# Flatcable_to_wires.net
KiCad netlist of a schematic drawn in Altium Designer
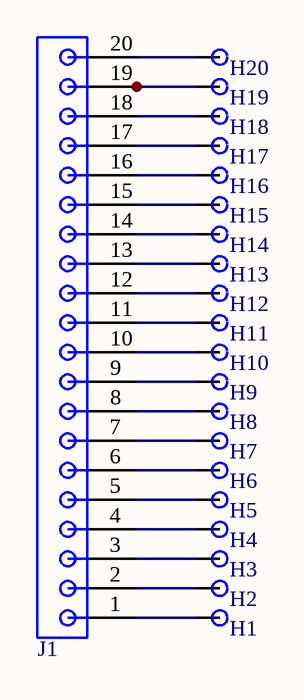
[diagram p0: Flatcable_to_wires.SchDoc]

(export (version "E")
  (design (tool "Eeschema 10.0.6"))
  (components
    (comp (ref "H1") (value "PAD") (footprint "PAD") (libsource (lib "sample_holder_library") (part "PAD")))
    (comp (ref "H2") (value "PAD") (footprint "PAD") (libsource (lib "sample_holder_library") (part "PAD")))
    (comp (ref "H3") (value "PAD") (footprint "PAD") (libsource (lib "sample_holder_library") (part "PAD")))
    (comp (ref "H4") (value "PAD") (footprint "PAD") (libsource (lib "sample_holder_library") (part "PAD")))
    (comp (ref "H5") (value "PAD") (footprint "PAD") (libsource (lib "sample_holder_library") (part "PAD")))
    (comp (ref "H6") (value "PAD") (footprint "PAD") (libsource (lib "sample_holder_library") (part "PAD")))
    (comp (ref "H7") (value "PAD") (footprint "PAD") (libsource (lib "sample_holder_library") (part "PAD")))
    (comp (ref "H8") (value "PAD") (footprint "PAD") (libsource (lib "sample_holder_library") (part "PAD")))
    (comp (ref "H9") (value "PAD") (footprint "PAD") (libsource (lib "sample_holder_library") (part "PAD")))
    (comp (ref "H10") (value "PAD") (footprint "PAD") (libsource (lib "sample_holder_library") (part "PAD")))
    (comp (ref "H11") (value "PAD") (footprint "PAD") (libsource (lib "sample_holder_library") (part "PAD")))
    (comp (ref "H12") (value "PAD") (footprint "PAD") (libsource (lib "sample_holder_library") (part "PAD")))
    (comp (ref "H13") (value "PAD") (footprint "PAD") (libsource (lib "sample_holder_library") (part "PAD")))
    (comp (ref "H14") (value "PAD") (footprint "PAD") (libsource (lib "sample_holder_library") (part "PAD")))
    (comp (ref "H15") (value "PAD") (footprint "PAD") (libsource (lib "sample_holder_library") (part "PAD")))
    (comp (ref "H16") (value "PAD") (footprint "PAD") (libsource (lib "sample_holder_library") (part "PAD")))
    (comp (ref "H17") (value "PAD") (footprint "PAD") (libsource (lib "sample_holder_library") (part "PAD")))
    (comp (ref "H18") (value "PAD") (footprint "PAD") (libsource (lib "sample_holder_library") (part "PAD")))
    (comp (ref "H19") (value "PAD") (footprint "PAD") (libsource (lib "sample_holder_library") (part "PAD")))
    (comp (ref "H20") (value "PAD") (footprint "PAD") (libsource (lib "sample_holder_library") (part "PAD")))
    (comp (ref "J1")
      (value "PADs for flat wire")
      (footprint "PADs for flat wire")
      (description "Pads for 20 pin, 0.635mm pitch flat wire.")
      (fields (field (name "PARTNUMBER") "52745-2097") (field (name "MANUFACTURER") "Molex"))
      (libsource (lib "sample_holder_library") (part "PADs for flat wire"))
    )
  )
  (nets
    (net (code "1") (name "Net-(H1-Pad1)") (class "Default")
      (node (ref "H1") (pin "1") (pinfunction "1_1") (pintype "passive"))
      (node (ref "J1") (pin "1") (pinfunction "1_1") (pintype "passive"))
    )
    (net (code "2") (name "Net-(H2-Pad1)") (class "Default")
      (node (ref "H2") (pin "1") (pinfunction "1_1") (pintype "passive"))
      (node (ref "J1") (pin "2") (pinfunction "2_2") (pintype "passive"))
    )
    (net (code "3") (name "Net-(H3-Pad1)") (class "Default")
      (node (ref "H3") (pin "1") (pinfunction "1_1") (pintype "passive"))
      (node (ref "J1") (pin "3") (pinfunction "3_3") (pintype "passive"))
    )
    (net (code "4") (name "Net-(H4-Pad1)") (class "Default")
      (node (ref "H4") (pin "1") (pinfunction "1_1") (pintype "passive"))
      (node (ref "J1") (pin "4") (pinfunction "4_4") (pintype "passive"))
    )
    (net (code "5") (name "Net-(H5-Pad1)") (class "Default")
      (node (ref "H5") (pin "1") (pinfunction "1_1") (pintype "passive"))
      (node (ref "J1") (pin "5") (pinfunction "5_5") (pintype "passive"))
    )
    (net (code "6") (name "Net-(H6-Pad1)") (class "Default")
      (node (ref "H6") (pin "1") (pinfunction "1_1") (pintype "passive"))
      (node (ref "J1") (pin "6") (pinfunction "6_6") (pintype "passive"))
    )
    (net (code "7") (name "Net-(H7-Pad1)") (class "Default")
      (node (ref "H7") (pin "1") (pinfunction "1_1") (pintype "passive"))
      (node (ref "J1") (pin "7") (pinfunction "7_7") (pintype "passive"))
    )
    (net (code "8") (name "Net-(H8-Pad1)") (class "Default")
      (node (ref "H8") (pin "1") (pinfunction "1_1") (pintype "passive"))
      (node (ref "J1") (pin "8") (pinfunction "8_8") (pintype "passive"))
    )
    (net (code "9") (name "Net-(H9-Pad1)") (class "Default")
      (node (ref "H9") (pin "1") (pinfunction "1_1") (pintype "passive"))
      (node (ref "J1") (pin "9") (pinfunction "9_9") (pintype "passive"))
    )
    (net (code "10") (name "Net-(H10-Pad1)") (class "Default")
      (node (ref "H10") (pin "1") (pinfunction "1_1") (pintype "passive"))
      (node (ref "J1") (pin "10") (pinfunction "10_10") (pintype "passive"))
    )
    (net (code "11") (name "Net-(H11-Pad1)") (class "Default")
      (node (ref "H11") (pin "1") (pinfunction "1_1") (pintype "passive"))
      (node (ref "J1") (pin "11") (pinfunction "11_11") (pintype "passive"))
    )
    (net (code "12") (name "Net-(H12-Pad1)") (class "Default")
      (node (ref "H12") (pin "1") (pinfunction "1_1") (pintype "passive"))
      (node (ref "J1") (pin "12") (pinfunction "12_12") (pintype "passive"))
    )
    (net (code "13") (name "Net-(H13-Pad1)") (class "Default")
      (node (ref "H13") (pin "1") (pinfunction "1_1") (pintype "passive"))
      (node (ref "J1") (pin "13") (pinfunction "13_13") (pintype "passive"))
    )
    (net (code "14") (name "Net-(H14-Pad1)") (class "Default")
      (node (ref "H14") (pin "1") (pinfunction "1_1") (pintype "passive"))
      (node (ref "J1") (pin "14") (pinfunction "14_14") (pintype "passive"))
    )
    (net (code "15") (name "Net-(H15-Pad1)") (class "Default")
      (node (ref "H15") (pin "1") (pinfunction "1_1") (pintype "passive"))
      (node (ref "J1") (pin "15") (pinfunction "15_15") (pintype "passive"))
    )
    (net (code "16") (name "Net-(H16-Pad1)") (class "Default")
      (node (ref "H16") (pin "1") (pinfunction "1_1") (pintype "passive"))
      (node (ref "J1") (pin "16") (pinfunction "16_16") (pintype "passive"))
    )
    (net (code "17") (name "Net-(H17-Pad1)") (class "Default")
      (node (ref "H17") (pin "1") (pinfunction "1_1") (pintype "passive"))
      (node (ref "J1") (pin "17") (pinfunction "17_17") (pintype "passive"))
    )
    (net (code "18") (name "Net-(H18-Pad1)") (class "Default")
      (node (ref "H18") (pin "1") (pinfunction "1_1") (pintype "passive"))
      (node (ref "J1") (pin "18") (pinfunction "18_18") (pintype "passive"))
    )
    (net (code "19") (name "Net-(H19-Pad1)") (class "Default")
      (node (ref "H19") (pin "1") (pinfunction "1_1") (pintype "passive"))
      (node (ref "J1") (pin "19") (pinfunction "19_19") (pintype "passive"))
    )
    (net (code "20") (name "Net-(H20-Pad1)") (class "Default")
      (node (ref "H20") (pin "1") (pinfunction "1_1") (pintype "passive"))
      (node (ref "J1") (pin "20") (pinfunction "20_20") (pintype "passive"))
    )
  )
)
